# wordclock_final.net
KiCad netlist of a schematic drawn in EAGLE
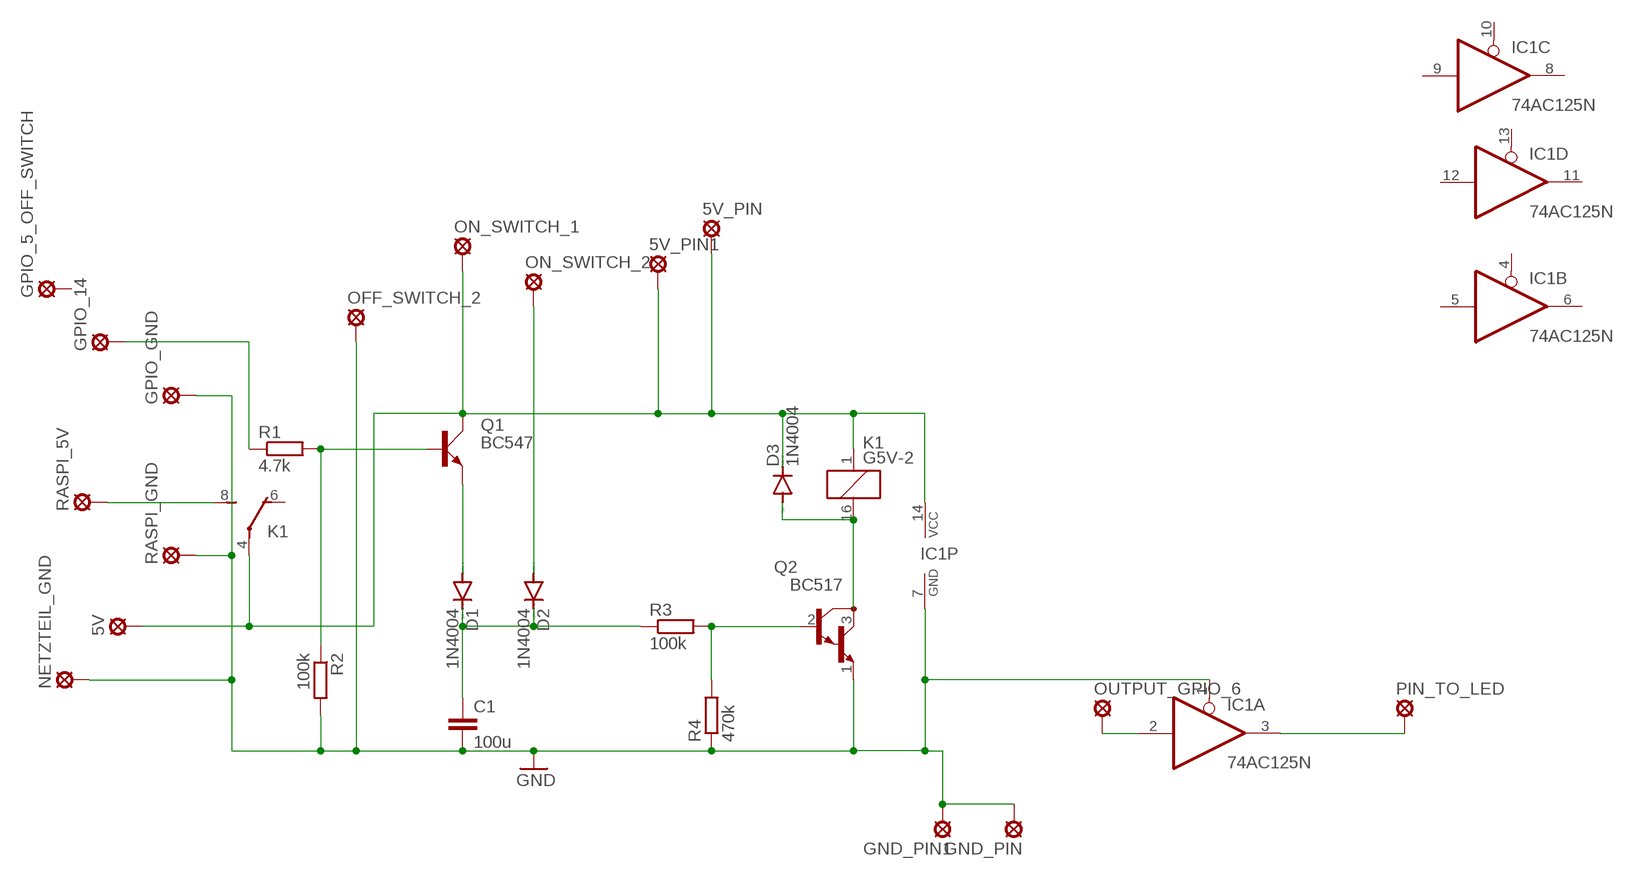
[diagram p0: schematic, sheet 1]

(export (version "E")
  (design (tool "Eeschema 10.0.6"))
  (components
    (comp (ref "5V")
      (value "SE14")
      (footprint "eagle-import:SE14")
      (libsource (lib "eagle-import") (part "SE14"))
    )
    (comp (ref "5V_PIN")
      (value "SE14")
      (footprint "eagle-import:SE14")
      (libsource (lib "eagle-import") (part "SE14"))
    )
    (comp (ref "5V_PIN1")
      (value "SE14")
      (footprint "eagle-import:SE14")
      (libsource (lib "eagle-import") (part "SE14"))
    )
    (comp (ref "C1")
      (value "100u")
      (footprint "eagle-import:C025-060X050")
      (libsource (lib "eagle-import") (part "C-EU025-060X050"))
    )
    (comp (ref "D1")
      (value "1N4004")
      (footprint "eagle-import:DO41-10")
      (libsource (lib "eagle-import") (part "1N4004"))
    )
    (comp (ref "D2")
      (value "1N4004")
      (footprint "eagle-import:DO41-10")
      (libsource (lib "eagle-import") (part "1N4004"))
    )
    (comp (ref "D3")
      (value "1N4004")
      (footprint "eagle-import:DO41-10")
      (libsource (lib "eagle-import") (part "1N4004"))
    )
    (comp (ref "GND_PIN")
      (value "SE14")
      (footprint "eagle-import:SE14")
      (libsource (lib "eagle-import") (part "SE14"))
    )
    (comp (ref "GND_PIN1")
      (value "SE14")
      (footprint "eagle-import:SE14")
      (libsource (lib "eagle-import") (part "SE14"))
    )
    (comp (ref "GPIO_5_OFF_SWITCH")
      (value "SE14")
      (footprint "eagle-import:SE14")
      (libsource (lib "eagle-import") (part "SE14"))
    )
    (comp (ref "GPIO_14")
      (value "SE14")
      (footprint "eagle-import:SE14")
      (libsource (lib "eagle-import") (part "SE14"))
    )
    (comp (ref "GPIO_GND")
      (value "SE14")
      (footprint "eagle-import:SE14")
      (libsource (lib "eagle-import") (part "SE14"))
    )
    (comp (ref "IC1")
      (value "74AC125N")
      (footprint "eagle-import:DIL14")
      (libsource (lib "eagle-import") (part "74125NAC"))
    )
    (comp (ref "K1")
      (value "G5V-2")
      (footprint "eagle-import:G5V-2")
      (fields (field (name "MPN") "G5V-2 5DC"))
      (libsource (lib "eagle-import") (part "G5V-2"))
    )
    (comp (ref "NETZTEIL_GND")
      (value "SE14")
      (footprint "eagle-import:SE14")
      (libsource (lib "eagle-import") (part "SE14"))
    )
    (comp (ref "OFF_SWITCH_2")
      (value "SE14")
      (footprint "eagle-import:SE14")
      (libsource (lib "eagle-import") (part "SE14"))
    )
    (comp (ref "ON_SWITCH_1")
      (value "SE14")
      (footprint "eagle-import:SE14")
      (libsource (lib "eagle-import") (part "SE14"))
    )
    (comp (ref "ON_SWITCH_2")
      (value "SE14")
      (footprint "eagle-import:SE14")
      (libsource (lib "eagle-import") (part "SE14"))
    )
    (comp (ref "OUTPUT_GPIO_6")
      (value "SE14")
      (footprint "eagle-import:SE14")
      (libsource (lib "eagle-import") (part "SE14"))
    )
    (comp (ref "PIN_TO_LED")
      (value "SE14")
      (footprint "eagle-import:SE14")
      (libsource (lib "eagle-import") (part "SE14"))
    )
    (comp (ref "Q1")
      (value "BC547")
      (footprint "eagle-import:SOT54A")
      (libsource (lib "eagle-import") (part "BC547"))
    )
    (comp (ref "Q2")
      (value "BC517")
      (footprint "eagle-import:TO92")
      (libsource (lib "eagle-import") (part "BC517"))
    )
    (comp (ref "R1")
      (value "4.7k")
      (footprint "eagle-import:0207_10")
      (libsource (lib "eagle-import") (part "R-EU_0207/10"))
    )
    (comp (ref "R2")
      (value "100k")
      (footprint "eagle-import:0207_10")
      (libsource (lib "eagle-import") (part "R-EU_0207/10"))
    )
    (comp (ref "R3")
      (value "100k")
      (footprint "eagle-import:0207_10")
      (libsource (lib "eagle-import") (part "R-EU_0207/10"))
    )
    (comp (ref "R4")
      (value "470k")
      (footprint "eagle-import:0207_10")
      (libsource (lib "eagle-import") (part "R-EU_0207/10"))
    )
    (comp (ref "RASPI_5V")
      (value "SE14")
      (footprint "eagle-import:SE14")
      (libsource (lib "eagle-import") (part "SE14"))
    )
    (comp (ref "RASPI_GND")
      (value "SE14")
      (footprint "eagle-import:SE14")
      (libsource (lib "eagle-import") (part "SE14"))
    )
  )
  (nets
    (net (code "1") (name "GND") (class "Default")
      (node (ref "C1") (pin "2") (pinfunction "2_2") (pintype "passive"))
      (node (ref "GND_PIN") (pin "MP") (pinfunction "MP_MP") (pintype "passive"))
      (node (ref "GND_PIN1") (pin "MP") (pinfunction "MP_MP") (pintype "passive"))
      (node (ref "GPIO_GND") (pin "MP") (pinfunction "MP_MP") (pintype "passive"))
      (node (ref "IC1") (pin "1") (pinfunction "OE_1") (pintype "input"))
      (node (ref "IC1") (pin "7") (pinfunction "GND_7") (pintype "power_in"))
      (node (ref "NETZTEIL_GND") (pin "MP") (pinfunction "MP_MP") (pintype "passive"))
      (node (ref "OFF_SWITCH_2") (pin "MP") (pinfunction "MP_MP") (pintype "passive"))
      (node (ref "Q2") (pin "1") (pinfunction "E_1") (pintype "passive"))
      (node (ref "R2") (pin "2") (pinfunction "2_2") (pintype "passive"))
      (node (ref "R4") (pin "1") (pinfunction "1_1") (pintype "passive"))
      (node (ref "RASPI_GND") (pin "MP") (pinfunction "MP_MP") (pintype "passive"))
    )
    (net (code "2") (name "Net-(C1-Pad1)") (class "Default")
      (node (ref "C1") (pin "1") (pinfunction "1_1") (pintype "passive"))
      (node (ref "D1") (pin "C") (pinfunction "C_C") (pintype "passive"))
      (node (ref "D2") (pin "C") (pinfunction "C_C") (pintype "passive"))
      (node (ref "R3") (pin "1") (pinfunction "1_1") (pintype "passive"))
    )
    (net (code "3") (name "Net-(D1-PadA)") (class "Default")
      (node (ref "D1") (pin "A") (pinfunction "A_A") (pintype "passive"))
      (node (ref "Q1") (pin "E") (pinfunction "E_E") (pintype "passive"))
    )
    (net (code "4") (name "Net-(D2-PadA)") (class "Default")
      (node (ref "D2") (pin "A") (pinfunction "A_A") (pintype "passive"))
      (node (ref "ON_SWITCH_2") (pin "MP") (pinfunction "MP_MP") (pintype "passive"))
    )
    (net (code "5") (name "Net-(GPIO_14-PadMP)") (class "Default")
      (node (ref "GPIO_14") (pin "MP") (pinfunction "MP_MP") (pintype "passive"))
      (node (ref "R1") (pin "1") (pinfunction "1_1") (pintype "passive"))
    )
    (net (code "6") (name "Net-(IC1A-I)") (class "Default")
      (node (ref "IC1") (pin "2") (pinfunction "I_2") (pintype "input"))
      (node (ref "OUTPUT_GPIO_6") (pin "MP") (pinfunction "MP_MP") (pintype "passive"))
    )
    (net (code "7") (name "Net-(IC1A-O)") (class "Default")
      (node (ref "IC1") (pin "3") (pinfunction "O_3") (pintype "tri_state"))
      (node (ref "PIN_TO_LED") (pin "MP") (pinfunction "MP_MP") (pintype "passive"))
    )
    (net (code "8") (name "Net-(IC1E-VCC)") (class "Default")
      (node (ref "5V") (pin "MP") (pinfunction "MP_MP") (pintype "passive"))
      (node (ref "5V_PIN") (pin "MP") (pinfunction "MP_MP") (pintype "passive"))
      (node (ref "5V_PIN1") (pin "MP") (pinfunction "MP_MP") (pintype "passive"))
      (node (ref "D3") (pin "C") (pinfunction "C_C") (pintype "passive"))
      (node (ref "IC1") (pin "14") (pinfunction "VCC_14") (pintype "power_in"))
      (node (ref "K1") (pin "1") (pinfunction "1_1") (pintype "passive"))
      (node (ref "K1") (pin "4") (pinfunction "P_4") (pintype "passive"))
      (node (ref "ON_SWITCH_1") (pin "MP") (pinfunction "MP_MP") (pintype "passive"))
      (node (ref "Q1") (pin "C") (pinfunction "C_C") (pintype "passive"))
    )
    (net (code "9") (name "Net-(K1A-S)") (class "Default")
      (node (ref "K1") (pin "8") (pinfunction "S_8") (pintype "passive"))
      (node (ref "RASPI_5V") (pin "MP") (pinfunction "MP_MP") (pintype "passive"))
    )
    (net (code "10") (name "Net-(K1C-2)") (class "Default")
      (node (ref "D3") (pin "A") (pinfunction "A_A") (pintype "passive"))
      (node (ref "K1") (pin "16") (pinfunction "2_16") (pintype "passive"))
      (node (ref "Q2") (pin "3") (pinfunction "C_3") (pintype "passive"))
    )
    (net (code "11") (name "Net-(Q1-PadB)") (class "Default")
      (node (ref "Q1") (pin "B") (pinfunction "B_B") (pintype "passive"))
      (node (ref "R1") (pin "2") (pinfunction "2_2") (pintype "passive"))
      (node (ref "R2") (pin "1") (pinfunction "1_1") (pintype "passive"))
    )
    (net (code "12") (name "Net-(Q2-B)") (class "Default")
      (node (ref "Q2") (pin "2") (pinfunction "B_2") (pintype "passive"))
      (node (ref "R3") (pin "2") (pinfunction "2_2") (pintype "passive"))
      (node (ref "R4") (pin "2") (pinfunction "2_2") (pintype "passive"))
    )
    (net (code "13") (name "unconnected-(GPIO_5_OFF_SWITCH-PadMP)") (class "Default")
      (node (ref "GPIO_5_OFF_SWITCH") (pin "MP") (pinfunction "MP_MP") (pintype "passive"))
    )
    (net (code "14") (name "unconnected-(IC1B-I-Pad5)") (class "Default")
      (node (ref "IC1") (pin "5") (pinfunction "I_5") (pintype "input"))
    )
    (net (code "15") (name "unconnected-(IC1B-O-Pad6)") (class "Default")
      (node (ref "IC1") (pin "6") (pinfunction "O_6") (pintype "tri_state"))
    )
    (net (code "16") (name "unconnected-(IC1B-OE-Pad4)") (class "Default")
      (node (ref "IC1") (pin "4") (pinfunction "OE_4") (pintype "input"))
    )
    (net (code "17") (name "unconnected-(IC1C-I-Pad9)") (class "Default")
      (node (ref "IC1") (pin "9") (pinfunction "I_9") (pintype "input"))
    )
    (net (code "18") (name "unconnected-(IC1C-O-Pad8)") (class "Default")
      (node (ref "IC1") (pin "8") (pinfunction "O_8") (pintype "tri_state"))
    )
    (net (code "19") (name "unconnected-(IC1C-OE-Pad10)") (class "Default")
      (node (ref "IC1") (pin "10") (pinfunction "OE_10") (pintype "input"))
    )
    (net (code "20") (name "unconnected-(IC1D-I-Pad12)") (class "Default")
      (node (ref "IC1") (pin "12") (pinfunction "I_12") (pintype "input"))
    )
    (net (code "21") (name "unconnected-(IC1D-O-Pad11)") (class "Default")
      (node (ref "IC1") (pin "11") (pinfunction "O_11") (pintype "tri_state"))
    )
    (net (code "22") (name "unconnected-(IC1D-OE-Pad13)") (class "Default")
      (node (ref "IC1") (pin "13") (pinfunction "OE_13") (pintype "input"))
    )
    (net (code "23") (name "unconnected-(K1A-O-Pad6)") (class "Default")
      (node (ref "K1") (pin "6") (pinfunction "O_6") (pintype "passive"))
    )
  )
)
